# Flipdot.net
KiCad netlist of a schematic drawn in EAGLE
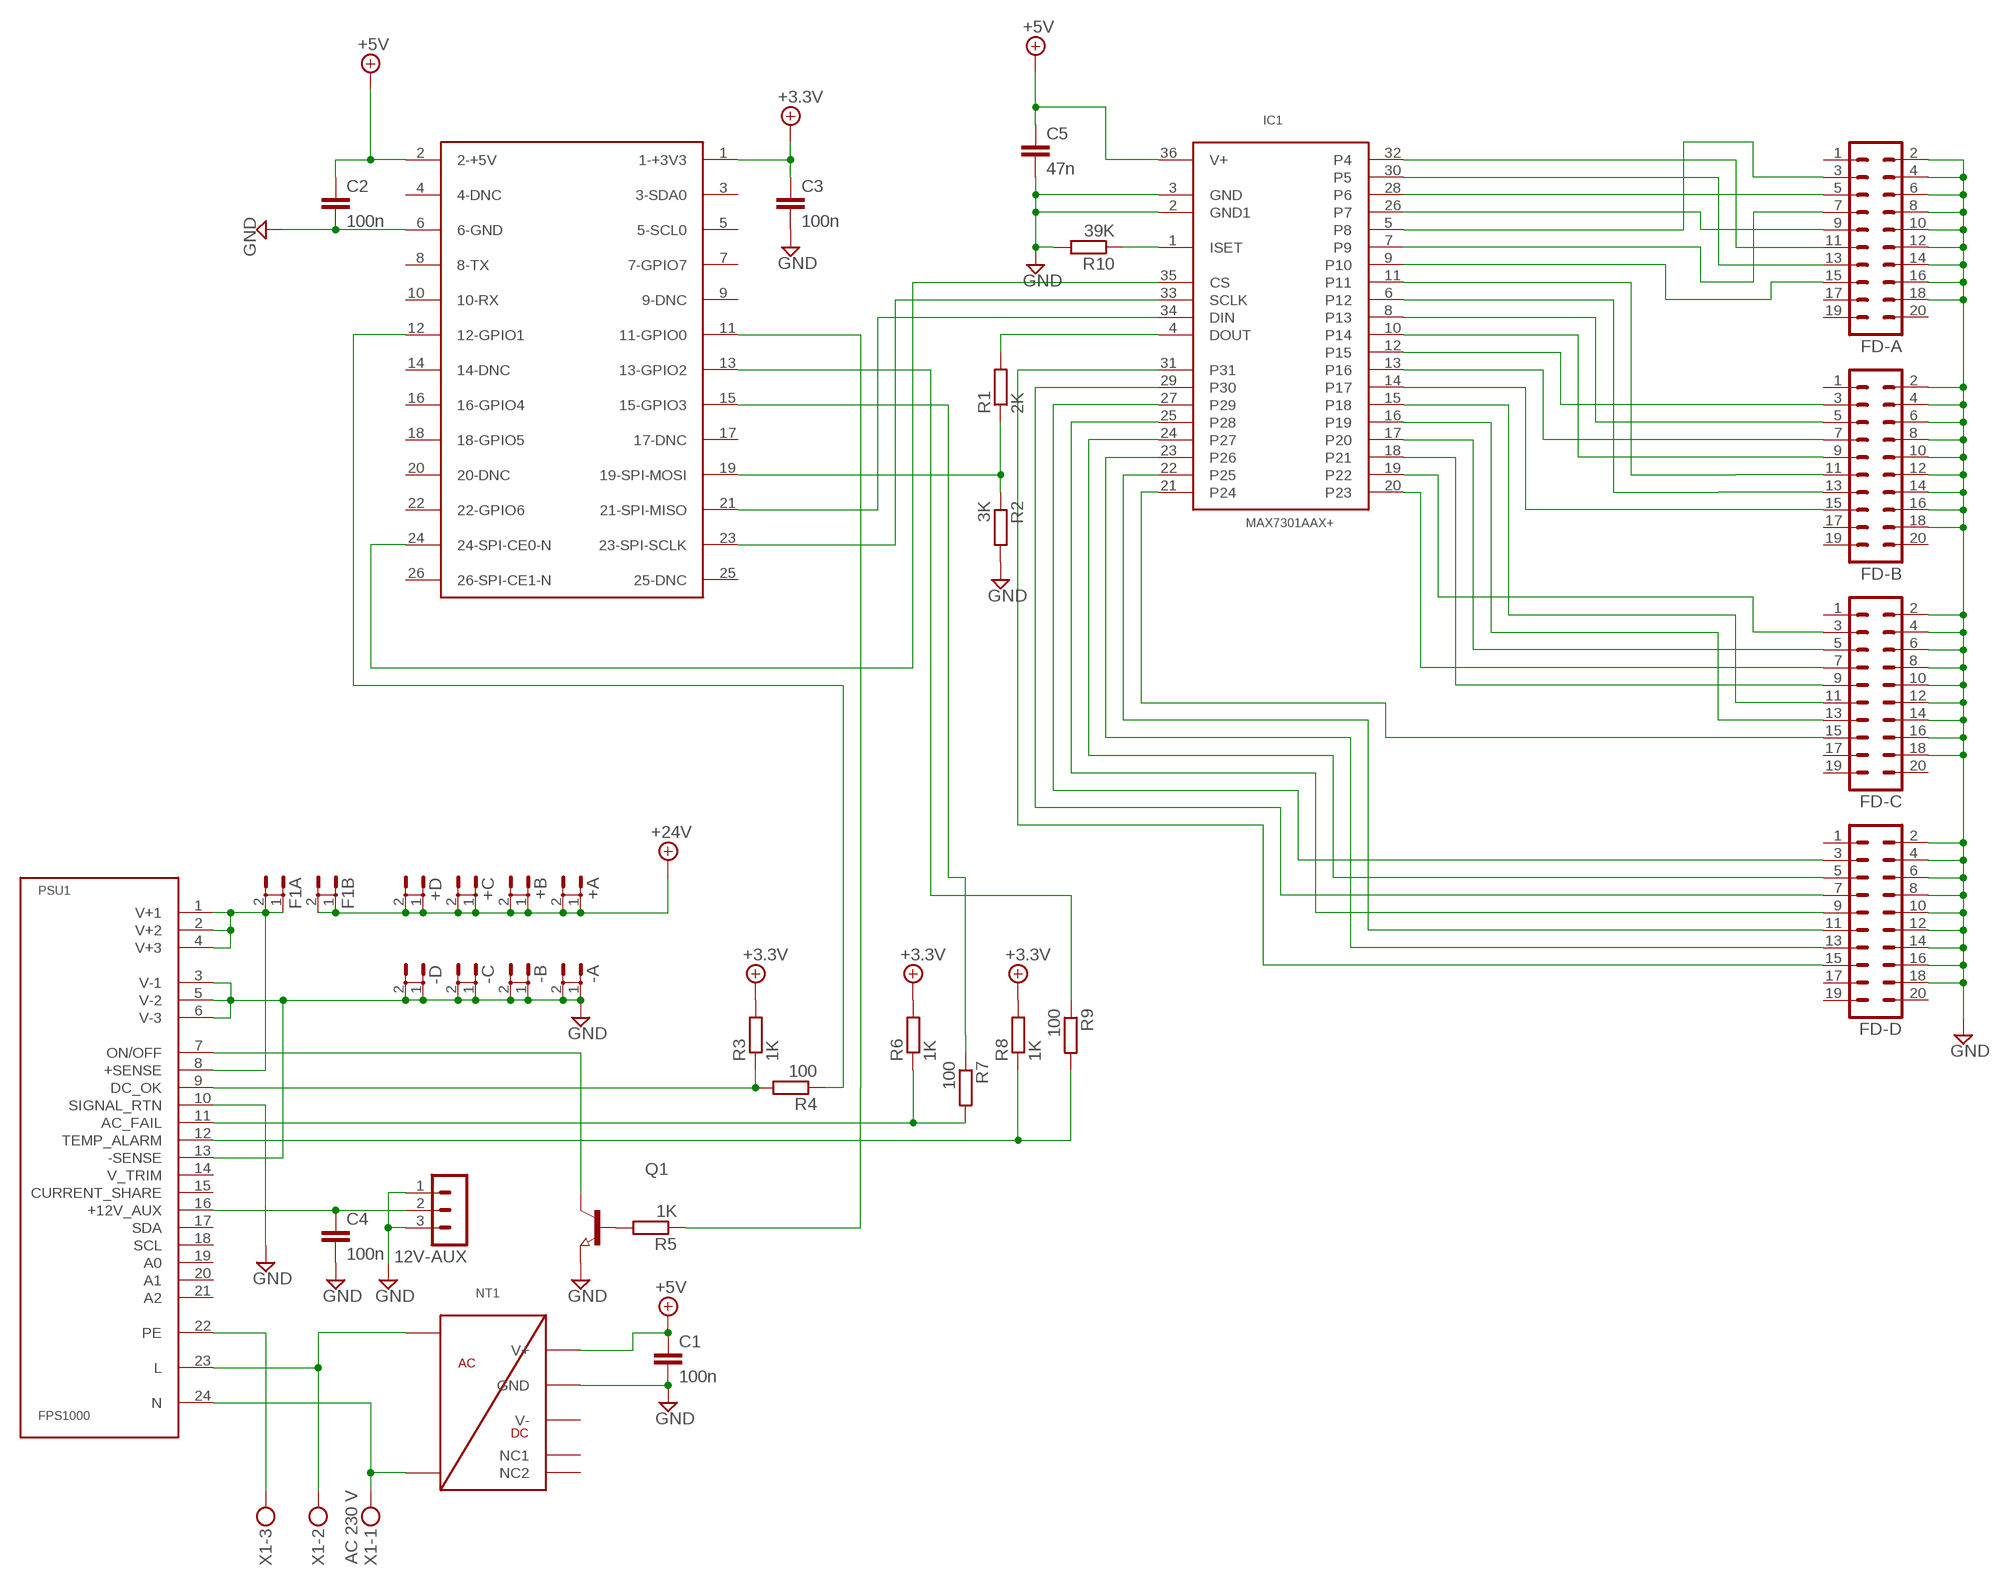
[diagram p0: schematic, sheet 1]

(export (version "E")
  (design (tool "Eeschema 10.0.6"))
  (components
    (comp (ref "+A")
      (value "ST6,3")
      (footprint "eagle-import:ST6,3")
      (libsource (lib "eagle-import") (part "ST6,3"))
    )
    (comp (ref "+B")
      (value "ST6,3")
      (footprint "eagle-import:ST6,3")
      (libsource (lib "eagle-import") (part "ST6,3"))
    )
    (comp (ref "+C")
      (value "ST6,3")
      (footprint "eagle-import:ST6,3")
      (libsource (lib "eagle-import") (part "ST6,3"))
    )
    (comp (ref "+D")
      (value "ST6,3")
      (footprint "eagle-import:ST6,3")
      (libsource (lib "eagle-import") (part "ST6,3"))
    )
    (comp (ref "-A")
      (value "ST6,3")
      (footprint "eagle-import:ST6,3")
      (libsource (lib "eagle-import") (part "ST6,3"))
    )
    (comp (ref "-B")
      (value "ST6,3")
      (footprint "eagle-import:ST6,3")
      (libsource (lib "eagle-import") (part "ST6,3"))
    )
    (comp (ref "-C")
      (value "ST6,3")
      (footprint "eagle-import:ST6,3")
      (libsource (lib "eagle-import") (part "ST6,3"))
    )
    (comp (ref "-D")
      (value "ST6,3")
      (footprint "eagle-import:ST6,3")
      (libsource (lib "eagle-import") (part "ST6,3"))
    )
    (comp (ref "12V-AUX")
      (value "MA03-1")
      (footprint "eagle-import:MA03-1")
      (libsource (lib "eagle-import") (part "MA03-1"))
    )
    (comp (ref "C1")
      (value "100n")
      (footprint "eagle-import:C0603")
      (libsource (lib "eagle-import") (part "C-EUC0603"))
    )
    (comp (ref "C2")
      (value "100n")
      (footprint "eagle-import:C0603")
      (libsource (lib "eagle-import") (part "C-EUC0603"))
    )
    (comp (ref "C3")
      (value "100n")
      (footprint "eagle-import:C0603")
      (libsource (lib "eagle-import") (part "C-EUC0603"))
    )
    (comp (ref "C4")
      (value "100n")
      (footprint "eagle-import:C0603")
      (libsource (lib "eagle-import") (part "C-EUC0603"))
    )
    (comp (ref "C5")
      (value "47n")
      (footprint "eagle-import:C0603")
      (libsource (lib "eagle-import") (part "C-EUC0603"))
    )
    (comp (ref "F1A")
      (value "ST6,3")
      (footprint "eagle-import:ST6,3")
      (libsource (lib "eagle-import") (part "ST6,3"))
    )
    (comp (ref "F1B")
      (value "ST6,3")
      (footprint "eagle-import:ST6,3")
      (libsource (lib "eagle-import") (part "ST6,3"))
    )
    (comp (ref "FD-A")
      (value "MA10-2")
      (footprint "eagle-import:MA10-2")
      (libsource (lib "eagle-import") (part "MA10-2"))
    )
    (comp (ref "FD-B")
      (value "MA10-2")
      (footprint "eagle-import:MA10-2")
      (fields (field (name "OC_FARNELL") "unknown") (field (name "OC_NEWARK") "unknown"))
      (libsource (lib "eagle-import") (part "MA10-2"))
    )
    (comp (ref "FD-C")
      (value "MA10-2")
      (footprint "eagle-import:MA10-2")
      (fields (field (name "OC_FARNELL") "unknown") (field (name "OC_NEWARK") "unknown"))
      (libsource (lib "eagle-import") (part "MA10-2"))
    )
    (comp (ref "FD-D")
      (value "MA10-2")
      (footprint "eagle-import:MA10-2")
      (fields (field (name "OC_FARNELL") "unknown") (field (name "OC_NEWARK") "unknown"))
      (libsource (lib "eagle-import") (part "MA10-2"))
    )
    (comp (ref "IC1")
      (value "MAX7301AAX+")
      (footprint "eagle-import:SSOP36")
      (libsource (lib "eagle-import") (part "MAX7301AAX+"))
    )
    (comp (ref "NT1")
      (value "TMPM04")
      (footprint "eagle-import:TPM04")
      (libsource (lib "eagle-import") (part "TMPM04"))
    )
    (comp (ref "PSU1")
      (value "FPS1000")
      (footprint "eagle-import:24W9F")
      (libsource (lib "eagle-import") (part "FPS1000"))
    )
    (comp (ref "Q1")
      (value "NPN-TRANSISTOR_SOT23")
      (footprint "eagle-import:SOT23")
      (libsource (lib "eagle-import") (part "NPN-TRANSISTOR_SOT23"))
    )
    (comp (ref "R1")
      (value "2K")
      (footprint "eagle-import:R0603")
      (libsource (lib "eagle-import") (part "R-EU_R0603"))
    )
    (comp (ref "R2")
      (value "3K")
      (footprint "eagle-import:R0603")
      (libsource (lib "eagle-import") (part "R-EU_R0603"))
    )
    (comp (ref "R3")
      (value "1K")
      (footprint "eagle-import:R0603")
      (libsource (lib "eagle-import") (part "R-EU_R0603"))
    )
    (comp (ref "R4")
      (value "100")
      (footprint "eagle-import:R0603")
      (libsource (lib "eagle-import") (part "R-EU_R0603"))
    )
    (comp (ref "R5")
      (value "1K")
      (footprint "eagle-import:R0603")
      (libsource (lib "eagle-import") (part "R-EU_R0603"))
    )
    (comp (ref "R6")
      (value "1K")
      (footprint "eagle-import:R0603")
      (libsource (lib "eagle-import") (part "R-EU_R0603"))
    )
    (comp (ref "R7")
      (value "100")
      (footprint "eagle-import:R0603")
      (libsource (lib "eagle-import") (part "R-EU_R0603"))
    )
    (comp (ref "R8")
      (value "1K")
      (footprint "eagle-import:R0603")
      (libsource (lib "eagle-import") (part "R-EU_R0603"))
    )
    (comp (ref "R9")
      (value "100")
      (footprint "eagle-import:R0603")
      (libsource (lib "eagle-import") (part "R-EU_R0603"))
    )
    (comp (ref "R10")
      (value "39K")
      (footprint "eagle-import:R0603")
      (libsource (lib "eagle-import") (part "R-EU_R0603"))
    )
    (comp (ref "U$1")
      (value "RASPBERRY-PI")
      (footprint "eagle-import:RASPBERRY-PI")
      (libsource (lib "eagle-import") (part "RASPBERRY-PI"))
    )
    (comp (ref "X1")
      (value "AC 230 V")
      (footprint "eagle-import:MKDSN1,5_3-5,08")
      (fields (field (name "MPN") "SMKDSN1,5/3-5,08"))
      (libsource (lib "eagle-import") (part "MKDSN1,5/3-5,08"))
    )
  )
  (nets
    (net (code "1") (name "+3.3V") (class "Default")
      (node (ref "C3") (pin "1") (pinfunction "1_1") (pintype "passive"))
      (node (ref "R3") (pin "2") (pinfunction "2_2") (pintype "passive"))
      (node (ref "R6") (pin "2") (pinfunction "2_2") (pintype "passive"))
      (node (ref "R8") (pin "2") (pinfunction "2_2") (pintype "passive"))
      (node (ref "U$1") (pin "1") (pinfunction "1-+3V3_1") (pintype "bidirectional"))
    )
    (net (code "2") (name "+5V") (class "Default")
      (node (ref "C1") (pin "1") (pinfunction "1_1") (pintype "passive"))
      (node (ref "C2") (pin "1") (pinfunction "1_1") (pintype "passive"))
      (node (ref "C5") (pin "1") (pinfunction "1_1") (pintype "passive"))
      (node (ref "IC1") (pin "36") (pinfunction "V+_36") (pintype "power_in"))
      (node (ref "NT1") (pin "3") (pinfunction "V+_3") (pintype "power_in"))
      (node (ref "U$1") (pin "2") (pinfunction "2-+5V_2") (pintype "bidirectional"))
    )
    (net (code "3") (name "+24V") (class "Default")
      (node (ref "+A") (pin "1") (pinfunction "1_1") (pintype "passive"))
      (node (ref "+A") (pin "2") (pinfunction "2_2") (pintype "passive"))
      (node (ref "+B") (pin "1") (pinfunction "1_1") (pintype "passive"))
      (node (ref "+B") (pin "2") (pinfunction "2_2") (pintype "passive"))
      (node (ref "+C") (pin "1") (pinfunction "1_1") (pintype "passive"))
      (node (ref "+C") (pin "2") (pinfunction "2_2") (pintype "passive"))
      (node (ref "+D") (pin "1") (pinfunction "1_1") (pintype "passive"))
      (node (ref "+D") (pin "2") (pinfunction "2_2") (pintype "passive"))
      (node (ref "F1B") (pin "1") (pinfunction "1_1") (pintype "passive"))
      (node (ref "F1B") (pin "2") (pinfunction "2_2") (pintype "passive"))
    )
    (net (code "4") (name "/NC1") (class "Default")
      (node (ref "NT1") (pin "1") (pinfunction "NC1_1") (pintype "power_in"))
    )
    (net (code "5") (name "/NC2") (class "Default")
      (node (ref "NT1") (pin "2") (pinfunction "NC2_2") (pintype "power_in"))
    )
    (net (code "6") (name "/V-") (class "Default")
      (node (ref "NT1") (pin "5") (pinfunction "V-_5") (pintype "power_in"))
    )
    (net (code "7") (name "GND") (class "Default")
      (node (ref "-A") (pin "1") (pinfunction "1_1") (pintype "passive"))
      (node (ref "-A") (pin "2") (pinfunction "2_2") (pintype "passive"))
      (node (ref "-B") (pin "1") (pinfunction "1_1") (pintype "passive"))
      (node (ref "-B") (pin "2") (pinfunction "2_2") (pintype "passive"))
      (node (ref "-C") (pin "1") (pinfunction "1_1") (pintype "passive"))
      (node (ref "-C") (pin "2") (pinfunction "2_2") (pintype "passive"))
      (node (ref "-D") (pin "1") (pinfunction "1_1") (pintype "passive"))
      (node (ref "-D") (pin "2") (pinfunction "2_2") (pintype "passive"))
      (node (ref "12V-AUX") (pin "1") (pinfunction "1_1") (pintype "passive"))
      (node (ref "12V-AUX") (pin "3") (pinfunction "3_3") (pintype "passive"))
      (node (ref "C1") (pin "2") (pinfunction "2_2") (pintype "passive"))
      (node (ref "C2") (pin "2") (pinfunction "2_2") (pintype "passive"))
      (node (ref "C3") (pin "2") (pinfunction "2_2") (pintype "passive"))
      (node (ref "C4") (pin "2") (pinfunction "2_2") (pintype "passive"))
      (node (ref "C5") (pin "2") (pinfunction "2_2") (pintype "passive"))
      (node (ref "FD-A") (pin "10") (pinfunction "10_10") (pintype "passive"))
      (node (ref "FD-A") (pin "12") (pinfunction "12_12") (pintype "passive"))
      (node (ref "FD-A") (pin "14") (pinfunction "14_14") (pintype "passive"))
      (node (ref "FD-A") (pin "16") (pinfunction "16_16") (pintype "passive"))
      (node (ref "FD-A") (pin "18") (pinfunction "18_18") (pintype "passive"))
      (node (ref "FD-A") (pin "2") (pinfunction "2_2") (pintype "passive"))
      (node (ref "FD-A") (pin "4") (pinfunction "4_4") (pintype "passive"))
      (node (ref "FD-A") (pin "6") (pinfunction "6_6") (pintype "passive"))
      (node (ref "FD-A") (pin "8") (pinfunction "8_8") (pintype "passive"))
      (node (ref "FD-B") (pin "10") (pinfunction "10_10") (pintype "passive"))
      (node (ref "FD-B") (pin "12") (pinfunction "12_12") (pintype "passive"))
      (node (ref "FD-B") (pin "14") (pinfunction "14_14") (pintype "passive"))
      (node (ref "FD-B") (pin "16") (pinfunction "16_16") (pintype "passive"))
      (node (ref "FD-B") (pin "18") (pinfunction "18_18") (pintype "passive"))
      (node (ref "FD-B") (pin "2") (pinfunction "2_2") (pintype "passive"))
      (node (ref "FD-B") (pin "4") (pinfunction "4_4") (pintype "passive"))
      (node (ref "FD-B") (pin "6") (pinfunction "6_6") (pintype "passive"))
      (node (ref "FD-B") (pin "8") (pinfunction "8_8") (pintype "passive"))
      (node (ref "FD-C") (pin "10") (pinfunction "10_10") (pintype "passive"))
      (node (ref "FD-C") (pin "12") (pinfunction "12_12") (pintype "passive"))
      (node (ref "FD-C") (pin "14") (pinfunction "14_14") (pintype "passive"))
      (node (ref "FD-C") (pin "16") (pinfunction "16_16") (pintype "passive"))
      (node (ref "FD-C") (pin "18") (pinfunction "18_18") (pintype "passive"))
      (node (ref "FD-C") (pin "2") (pinfunction "2_2") (pintype "passive"))
      (node (ref "FD-C") (pin "4") (pinfunction "4_4") (pintype "passive"))
      (node (ref "FD-C") (pin "6") (pinfunction "6_6") (pintype "passive"))
      (node (ref "FD-C") (pin "8") (pinfunction "8_8") (pintype "passive"))
      (node (ref "FD-D") (pin "10") (pinfunction "10_10") (pintype "passive"))
      (node (ref "FD-D") (pin "12") (pinfunction "12_12") (pintype "passive"))
      (node (ref "FD-D") (pin "14") (pinfunction "14_14") (pintype "passive"))
      (node (ref "FD-D") (pin "16") (pinfunction "16_16") (pintype "passive"))
      (node (ref "FD-D") (pin "18") (pinfunction "18_18") (pintype "passive"))
      (node (ref "FD-D") (pin "2") (pinfunction "2_2") (pintype "passive"))
      (node (ref "FD-D") (pin "4") (pinfunction "4_4") (pintype "passive"))
      (node (ref "FD-D") (pin "6") (pinfunction "6_6") (pintype "passive"))
      (node (ref "FD-D") (pin "8") (pinfunction "8_8") (pintype "passive"))
      (node (ref "IC1") (pin "2") (pinfunction "GND1_2") (pintype "power_in"))
      (node (ref "IC1") (pin "3") (pinfunction "GND_3") (pintype "power_in"))
      (node (ref "NT1") (pin "4") (pinfunction "GND_4") (pintype "power_in"))
      (node (ref "PSU1") (pin "10") (pinfunction "SIGNAL_RTN_10") (pintype "bidirectional"))
      (node (ref "PSU1") (pin "13") (pinfunction "-SENSE_13") (pintype "bidirectional"))
      (node (ref "PSU1") (pin "3") (pinfunction "V-1_3") (pintype "power_in"))
      (node (ref "PSU1") (pin "5") (pinfunction "V-2_5") (pintype "power_in"))
      (node (ref "PSU1") (pin "6") (pinfunction "V-3_6") (pintype "power_in"))
      (node (ref "Q1") (pin "2") (pinfunction "E_2") (pintype "passive"))
      (node (ref "R10") (pin "2") (pinfunction "2_2") (pintype "passive"))
      (node (ref "R2") (pin "2") (pinfunction "2_2") (pintype "passive"))
      (node (ref "U$1") (pin "6") (pinfunction "6-GND_6") (pintype "bidirectional"))
    )
    (net (code "8") (name "Net-(IC1-CS)") (class "Default")
      (node (ref "IC1") (pin "35") (pinfunction "CS_35") (pintype "bidirectional"))
      (node (ref "U$1") (pin "24") (pinfunction "24-SPI-CE0-N_24") (pintype "bidirectional"))
    )
    (net (code "9") (name "Net-(IC1-DIN)") (class "Default")
      (node (ref "IC1") (pin "34") (pinfunction "DIN_34") (pintype "bidirectional"))
      (node (ref "U$1") (pin "21") (pinfunction "21-SPI-MISO_21") (pintype "bidirectional"))
    )
    (net (code "10") (name "Net-(IC1-DOUT)") (class "Default")
      (node (ref "IC1") (pin "4") (pinfunction "DOUT_4") (pintype "bidirectional"))
      (node (ref "R1") (pin "2") (pinfunction "2_2") (pintype "passive"))
    )
    (net (code "11") (name "Net-(IC1-ISET)") (class "Default")
      (node (ref "IC1") (pin "1") (pinfunction "ISET_1") (pintype "bidirectional"))
      (node (ref "R10") (pin "1") (pinfunction "1_1") (pintype "passive"))
    )
    (net (code "12") (name "Net-(IC1-P4)") (class "Default")
      (node (ref "FD-A") (pin "11") (pinfunction "11_11") (pintype "passive"))
      (node (ref "IC1") (pin "32") (pinfunction "P4_32") (pintype "bidirectional"))
    )
    (net (code "13") (name "Net-(IC1-P5)") (class "Default")
      (node (ref "FD-A") (pin "13") (pinfunction "13_13") (pintype "passive"))
      (node (ref "IC1") (pin "30") (pinfunction "P5_30") (pintype "bidirectional"))
    )
    (net (code "14") (name "Net-(IC1-P6)") (class "Default")
      (node (ref "FD-A") (pin "5") (pinfunction "5_5") (pintype "passive"))
      (node (ref "IC1") (pin "28") (pinfunction "P6_28") (pintype "bidirectional"))
    )
    (net (code "15") (name "Net-(IC1-P7)") (class "Default")
      (node (ref "FD-A") (pin "9") (pinfunction "9_9") (pintype "passive"))
      (node (ref "IC1") (pin "26") (pinfunction "P7_26") (pintype "bidirectional"))
    )
    (net (code "16") (name "Net-(IC1-P8)") (class "Default")
      (node (ref "FD-A") (pin "3") (pinfunction "3_3") (pintype "passive"))
      (node (ref "IC1") (pin "5") (pinfunction "P8_5") (pintype "bidirectional"))
    )
    (net (code "17") (name "Net-(IC1-P9)") (class "Default")
      (node (ref "FD-A") (pin "7") (pinfunction "7_7") (pintype "passive"))
      (node (ref "IC1") (pin "7") (pinfunction "P9_7") (pintype "bidirectional"))
    )
    (net (code "18") (name "Net-(IC1-P10)") (class "Default")
      (node (ref "FD-A") (pin "15") (pinfunction "15_15") (pintype "passive"))
      (node (ref "IC1") (pin "9") (pinfunction "P10_9") (pintype "bidirectional"))
    )
    (net (code "19") (name "Net-(IC1-P11)") (class "Default")
      (node (ref "FD-B") (pin "11") (pinfunction "11_11") (pintype "passive"))
      (node (ref "IC1") (pin "11") (pinfunction "P11_11") (pintype "bidirectional"))
    )
    (net (code "20") (name "Net-(IC1-P12)") (class "Default")
      (node (ref "FD-B") (pin "13") (pinfunction "13_13") (pintype "passive"))
      (node (ref "IC1") (pin "6") (pinfunction "P12_6") (pintype "bidirectional"))
    )
    (net (code "21") (name "Net-(IC1-P13)") (class "Default")
      (node (ref "FD-B") (pin "5") (pinfunction "5_5") (pintype "passive"))
      (node (ref "IC1") (pin "8") (pinfunction "P13_8") (pintype "bidirectional"))
    )
    (net (code "22") (name "Net-(IC1-P14)") (class "Default")
      (node (ref "FD-B") (pin "9") (pinfunction "9_9") (pintype "passive"))
      (node (ref "IC1") (pin "10") (pinfunction "P14_10") (pintype "bidirectional"))
    )
    (net (code "23") (name "Net-(IC1-P15)") (class "Default")
      (node (ref "FD-B") (pin "3") (pinfunction "3_3") (pintype "passive"))
      (node (ref "IC1") (pin "12") (pinfunction "P15_12") (pintype "bidirectional"))
    )
    (net (code "24") (name "Net-(IC1-P16)") (class "Default")
      (node (ref "FD-B") (pin "7") (pinfunction "7_7") (pintype "passive"))
      (node (ref "IC1") (pin "13") (pinfunction "P16_13") (pintype "bidirectional"))
    )
    (net (code "25") (name "Net-(IC1-P17)") (class "Default")
      (node (ref "FD-B") (pin "15") (pinfunction "15_15") (pintype "passive"))
      (node (ref "IC1") (pin "14") (pinfunction "P17_14") (pintype "bidirectional"))
    )
    (net (code "26") (name "Net-(IC1-P18)") (class "Default")
      (node (ref "FD-C") (pin "11") (pinfunction "11_11") (pintype "passive"))
      (node (ref "IC1") (pin "15") (pinfunction "P18_15") (pintype "bidirectional"))
    )
    (net (code "27") (name "Net-(IC1-P19)") (class "Default")
      (node (ref "FD-C") (pin "13") (pinfunction "13_13") (pintype "passive"))
      (node (ref "IC1") (pin "16") (pinfunction "P19_16") (pintype "bidirectional"))
    )
    (net (code "28") (name "Net-(IC1-P20)") (class "Default")
      (node (ref "FD-C") (pin "5") (pinfunction "5_5") (pintype "passive"))
      (node (ref "IC1") (pin "17") (pinfunction "P20_17") (pintype "bidirectional"))
    )
    (net (code "29") (name "Net-(IC1-P21)") (class "Default")
      (node (ref "FD-C") (pin "9") (pinfunction "9_9") (pintype "passive"))
      (node (ref "IC1") (pin "18") (pinfunction "P21_18") (pintype "bidirectional"))
    )
    (net (code "30") (name "Net-(IC1-P22)") (class "Default")
      (node (ref "FD-C") (pin "3") (pinfunction "3_3") (pintype "passive"))
      (node (ref "IC1") (pin "19") (pinfunction "P22_19") (pintype "bidirectional"))
    )
    (net (code "31") (name "Net-(IC1-P23)") (class "Default")
      (node (ref "FD-C") (pin "7") (pinfunction "7_7") (pintype "passive"))
      (node (ref "IC1") (pin "20") (pinfunction "P23_20") (pintype "bidirectional"))
    )
    (net (code "32") (name "Net-(IC1-P24)") (class "Default")
      (node (ref "FD-C") (pin "15") (pinfunction "15_15") (pintype "passive"))
      (node (ref "IC1") (pin "21") (pinfunction "P24_21") (pintype "bidirectional"))
    )
    (net (code "33") (name "Net-(IC1-P25)") (class "Default")
      (node (ref "FD-D") (pin "11") (pinfunction "11_11") (pintype "passive"))
      (node (ref "IC1") (pin "22") (pinfunction "P25_22") (pintype "bidirectional"))
    )
    (net (code "34") (name "Net-(IC1-P26)") (class "Default")
      (node (ref "FD-D") (pin "13") (pinfunction "13_13") (pintype "passive"))
      (node (ref "IC1") (pin "23") (pinfunction "P26_23") (pintype "bidirectional"))
    )
    (net (code "35") (name "Net-(IC1-P27)") (class "Default")
      (node (ref "FD-D") (pin "5") (pinfunction "5_5") (pintype "passive"))
      (node (ref "IC1") (pin "24") (pinfunction "P27_24") (pintype "bidirectional"))
    )
    (net (code "36") (name "Net-(IC1-P28)") (class "Default")
      (node (ref "FD-D") (pin "9") (pinfunction "9_9") (pintype "passive"))
      (node (ref "IC1") (pin "25") (pinfunction "P28_25") (pintype "bidirectional"))
    )
    (net (code "37") (name "Net-(IC1-P29)") (class "Default")
      (node (ref "FD-D") (pin "3") (pinfunction "3_3") (pintype "passive"))
      (node (ref "IC1") (pin "27") (pinfunction "P29_27") (pintype "bidirectional"))
    )
    (net (code "38") (name "Net-(IC1-P30)") (class "Default")
      (node (ref "FD-D") (pin "7") (pinfunction "7_7") (pintype "passive"))
      (node (ref "IC1") (pin "29") (pinfunction "P30_29") (pintype "bidirectional"))
    )
    (net (code "39") (name "Net-(IC1-P31)") (class "Default")
      (node (ref "FD-D") (pin "15") (pinfunction "15_15") (pintype "passive"))
      (node (ref "IC1") (pin "31") (pinfunction "P31_31") (pintype "bidirectional"))
    )
    (net (code "40") (name "Net-(IC1-SCLK)") (class "Default")
      (node (ref "IC1") (pin "33") (pinfunction "SCLK_33") (pintype "bidirectional"))
      (node (ref "U$1") (pin "23") (pinfunction "23-SPI-SCLK_23") (pintype "bidirectional"))
    )
    (net (code "41") (name "Net-(NT1-L)") (class "Default")
      (node (ref "NT1") (pin "7") (pinfunction "L_7") (pintype "power_in"))
      (node (ref "PSU1") (pin "23") (pinfunction "L_23") (pintype "bidirectional"))
      (node (ref "X1") (pin "2") (pinfunction "KL_2") (pintype "passive"))
    )
    (net (code "42") (name "Net-(NT1-N)") (class "Default")
      (node (ref "NT1") (pin "6") (pinfunction "N_6") (pintype "power_in"))
      (node (ref "PSU1") (pin "24") (pinfunction "N_24") (pintype "bidirectional"))
      (node (ref "X1") (pin "1") (pinfunction "KL_1") (pintype "passive"))
    )
    (net (code "43") (name "Net-(PSU1-+12V_AUX)") (class "Default")
      (node (ref "12V-AUX") (pin "2") (pinfunction "2_2") (pintype "passive"))
      (node (ref "C4") (pin "1") (pinfunction "1_1") (pintype "passive"))
      (node (ref "PSU1") (pin "16") (pinfunction "+12V_AUX_16") (pintype "bidirectional"))
    )
    (net (code "44") (name "Net-(PSU1-+SENSE)") (class "Default")
      (node (ref "F1A") (pin "1") (pinfunction "1_1") (pintype "passive"))
      (node (ref "F1A") (pin "2") (pinfunction "2_2") (pintype "passive"))
      (node (ref "PSU1") (pin "1") (pinfunction "V+1_1") (pintype "power_in"))
      (node (ref "PSU1") (pin "2") (pinfunction "V+2_2") (pintype "power_in"))
      (node (ref "PSU1") (pin "4") (pinfunction "V+3_4") (pintype "power_in"))
      (node (ref "PSU1") (pin "8") (pinfunction "+SENSE_8") (pintype "bidirectional"))
    )
    (net (code "45") (name "Net-(PSU1-AC_FAIL)") (class "Default")
      (node (ref "PSU1") (pin "11") (pinfunction "AC_FAIL_11") (pintype "bidirectional"))
      (node (ref "R6") (pin "1") (pinfunction "1_1") (pintype "passive"))
      (node (ref "R7") (pin "2") (pinfunction "2_2") (pintype "passive"))
    )
    (net (code "46") (name "Net-(PSU1-DC_OK)") (class "Default")
      (node (ref "PSU1") (pin "9") (pinfunction "DC_OK_9") (pintype "bidirectional"))
      (node (ref "R3") (pin "1") (pinfunction "1_1") (pintype "passive"))
      (node (ref "R4") (pin "2") (pinfunction "2_2") (pintype "passive"))
    )
    (net (code "47") (name "Net-(PSU1-ON{slash}OFF)") (class "Default")
      (node (ref "PSU1") (pin "7") (pinfunction "ON/OFF_7") (pintype "bidirectional"))
      (node (ref "Q1") (pin "3") (pinfunction "C_3") (pintype "passive"))
    )
    (net (code "48") (name "Net-(PSU1-PE)") (class "Default")
      (node (ref "PSU1") (pin "22") (pinfunction "PE_22") (pintype "bidirectional"))
      (node (ref "X1") (pin "3") (pinfunction "KL_3") (pintype "passive"))
    )
    (net (code "49") (name "Net-(PSU1-TEMP_ALARM)") (class "Default")
      (node (ref "PSU1") (pin "12") (pinfunction "TEMP_ALARM_12") (pintype "bidirectional"))
      (node (ref "R8") (pin "1") (pinfunction "1_1") (pintype "passive"))
      (node (ref "R9") (pin "2") (pinfunction "2_2") (pintype "passive"))
    )
    (net (code "50") (name "Net-(Q1-B)") (class "Default")
      (node (ref "Q1") (pin "1") (pinfunction "B_1") (pintype "passive"))
      (node (ref "R5") (pin "2") (pinfunction "2_2") (pintype "passive"))
    )
    (net (code "51") (name "Net-(U$1-11-GPIO0)") (class "Default")
      (node (ref "R5") (pin "1") (pinfunction "1_1") (pintype "passive"))
      (node (ref "U$1") (pin "11") (pinfunction "11-GPIO0_11") (pintype "bidirectional"))
    )
    (net (code "52") (name "Net-(U$1-12-GPIO1)") (class "Default")
      (node (ref "R4") (pin "1") (pinfunction "1_1") (pintype "passive"))
      (node (ref "U$1") (pin "12") (pinfunction "12-GPIO1_12") (pintype "bidirectional"))
    )
    (net (code "53") (name "Net-(U$1-13-GPIO2)") (class "Default")
      (node (ref "R9") (pin "1") (pinfunction "1_1") (pintype "passive"))
      (node (ref "U$1") (pin "13") (pinfunction "13-GPIO2_13") (pintype "bidirectional"))
    )
    (net (code "54") (name "Net-(U$1-15-GPIO3)") (class "Default")
      (node (ref "R7") (pin "1") (pinfunction "1_1") (pintype "passive"))
      (node (ref "U$1") (pin "15") (pinfunction "15-GPIO3_15") (pintype "bidirectional"))
    )
    (net (code "55") (name "Net-(U$1-19-SPI-MOSI)") (class "Default")
      (node (ref "R1") (pin "1") (pinfunction "1_1") (pintype "passive"))
      (node (ref "R2") (pin "1") (pinfunction "1_1") (pintype "passive"))
      (node (ref "U$1") (pin "19") (pinfunction "19-SPI-MOSI_19") (pintype "bidirectional"))
    )
    (net (code "56") (name "unconnected-(FD-A-Pad1)") (class "Default")
      (node (ref "FD-A") (pin "1") (pinfunction "1_1") (pintype "passive"))
    )
    (net (code "57") (name "unconnected-(FD-A-Pad17)") (class "Default")
      (node (ref "FD-A") (pin "17") (pinfunction "17_17") (pintype "passive"))
    )
    (net (code "58") (name "unconnected-(FD-A-Pad19)") (class "Default")
      (node (ref "FD-A") (pin "19") (pinfunction "19_19") (pintype "passive"))
    )
    (net (code "59") (name "unconnected-(FD-A-Pad20)") (class "Default")
      (node (ref "FD-A") (pin "20") (pinfunction "20_20") (pintype "passive"))
    )
    (net (code "60") (name "unconnected-(FD-B-Pad1)") (class "Default")
      (node (ref "FD-B") (pin "1") (pinfunction "1_1") (pintype "passive"))
    )
    (net (code "61") (name "unconnected-(FD-B-Pad17)") (class "Default")
      (node (ref "FD-B") (pin "17") (pinfunction "17_17") (pintype "passive"))
    )
    (net (code "62") (name "unconnected-(FD-B-Pad19)") (class "Default")
      (node (ref "FD-B") (pin "19") (pinfunction "19_19") (pintype "passive"))
    )
    (net (code "63") (name "unconnected-(FD-B-Pad20)") (class "Default")
      (node (ref "FD-B") (pin "20") (pinfunction "20_20") (pintype "passive"))
    )
    (net (code "64") (name "unconnected-(FD-C-Pad1)") (class "Default")
      (node (ref "FD-C") (pin "1") (pinfunction "1_1") (pintype "passive"))
    )
    (net (code "65") (name "unconnected-(FD-C-Pad17)") (class "Default")
      (node (ref "FD-C") (pin "17") (pinfunction "17_17") (pintype "passive"))
    )
    (net (code "66") (name "unconnected-(FD-C-Pad19)") (class "Default")
      (node (ref "FD-C") (pin "19") (pinfunction "19_19") (pintype "passive"))
    )
    (net (code "67") (name "unconnected-(FD-C-Pad20)") (class "Default")
      (node (ref "FD-C") (pin "20") (pinfunction "20_20") (pintype "passive"))
    )
    (net (code "68") (name "unconnected-(FD-D-Pad1)") (class "Default")
      (node (ref "FD-D") (pin "1") (pinfunction "1_1") (pintype "passive"))
    )
    (net (code "69") (name "unconnected-(FD-D-Pad17)") (class "Default")
      (node (ref "FD-D") (pin "17") (pinfunction "17_17") (pintype "passive"))
    )
    (net (code "70") (name "unconnected-(FD-D-Pad19)") (class "Default")
      (node (ref "FD-D") (pin "19") (pinfunction "19_19") (pintype "passive"))
    )
    (net (code "71") (name "unconnected-(FD-D-Pad20)") (class "Default")
      (node (ref "FD-D") (pin "20") (pinfunction "20_20") (pintype "passive"))
    )
    (net (code "72") (name "unconnected-(PSU1-A0-Pad19)") (class "Default")
      (node (ref "PSU1") (pin "19") (pinfunction "A0_19") (pintype "bidirectional"))
    )
    (net (code "73") (name "unconnected-(PSU1-A1-Pad20)") (class "Default")
      (node (ref "PSU1") (pin "20") (pinfunction "A1_20") (pintype "bidirectional"))
    )
    (net (code "74") (name "unconnected-(PSU1-A2-Pad21)") (class "Default")
      (node (ref "PSU1") (pin "21") (pinfunction "A2_21") (pintype "bidirectional"))
    )
    (net (code "75") (name "unconnected-(PSU1-CURRENT_SHARE-Pad15)") (class "Default")
      (node (ref "PSU1") (pin "15") (pinfunction "CURRENT_SHARE_15") (pintype "bidirectional"))
    )
    (net (code "76") (name "unconnected-(PSU1-SCL-Pad18)") (class "Default")
      (node (ref "PSU1") (pin "18") (pinfunction "SCL_18") (pintype "bidirectional"))
    )
    (net (code "77") (name "unconnected-(PSU1-SDA-Pad17)") (class "Default")
      (node (ref "PSU1") (pin "17") (pinfunction "SDA_17") (pintype "bidirectional"))
    )
    (net (code "78") (name "unconnected-(PSU1-V_TRIM-Pad14)") (class "Default")
      (node (ref "PSU1") (pin "14") (pinfunction "V_TRIM_14") (pintype "bidirectional"))
    )
    (net (code "79") (name "unconnected-(U$1-3-SDA0-Pad3)") (class "Default")
      (node (ref "U$1") (pin "3") (pinfunction "3-SDA0_3") (pintype "bidirectional"))
    )
    (net (code "80") (name "unconnected-(U$1-4-DNC-Pad4)") (class "Default")
      (node (ref "U$1") (pin "4") (pinfunction "4-DNC_4") (pintype "bidirectional"))
    )
    (net (code "81") (name "unconnected-(U$1-5-SCL0-Pad5)") (class "Default")
      (node (ref "U$1") (pin "5") (pinfunction "5-SCL0_5") (pintype "bidirectional"))
    )
    (net (code "82") (name "unconnected-(U$1-7-GPIO7-Pad7)") (class "Default")
      (node (ref "U$1") (pin "7") (pinfunction "7-GPIO7_7") (pintype "bidirectional"))
    )
    (net (code "83") (name "unconnected-(U$1-8-TX-Pad8)") (class "Default")
      (node (ref "U$1") (pin "8") (pinfunction "8-TX_8") (pintype "bidirectional"))
    )
    (net (code "84") (name "unconnected-(U$1-9-DNC-Pad9)") (class "Default")
      (node (ref "U$1") (pin "9") (pinfunction "9-DNC_9") (pintype "bidirectional"))
    )
    (net (code "85") (name "unconnected-(U$1-10-RX-Pad10)") (class "Default")
      (node (ref "U$1") (pin "10") (pinfunction "10-RX_10") (pintype "bidirectional"))
    )
    (net (code "86") (name "unconnected-(U$1-14-DNC-Pad14)") (class "Default")
      (node (ref "U$1") (pin "14") (pinfunction "14-DNC_14") (pintype "bidirectional"))
    )
    (net (code "87") (name "unconnected-(U$1-16-GPIO4-Pad16)") (class "Default")
      (node (ref "U$1") (pin "16") (pinfunction "16-GPIO4_16") (pintype "bidirectional"))
    )
    (net (code "88") (name "unconnected-(U$1-17-DNC-Pad17)") (class "Default")
      (node (ref "U$1") (pin "17") (pinfunction "17-DNC_17") (pintype "bidirectional"))
    )
    (net (code "89") (name "unconnected-(U$1-18-GPIO5-Pad18)") (class "Default")
      (node (ref "U$1") (pin "18") (pinfunction "18-GPIO5_18") (pintype "bidirectional"))
    )
    (net (code "90") (name "unconnected-(U$1-20-DNC-Pad20)") (class "Default")
      (node (ref "U$1") (pin "20") (pinfunction "20-DNC_20") (pintype "bidirectional"))
    )
    (net (code "91") (name "unconnected-(U$1-22-GPIO6-Pad22)") (class "Default")
      (node (ref "U$1") (pin "22") (pinfunction "22-GPIO6_22") (pintype "bidirectional"))
    )
    (net (code "92") (name "unconnected-(U$1-25-DNC-Pad25)") (class "Default")
      (node (ref "U$1") (pin "25") (pinfunction "25-DNC_25") (pintype "bidirectional"))
    )
    (net (code "93") (name "unconnected-(U$1-26-SPI-CE1-N-Pad26)") (class "Default")
      (node (ref "U$1") (pin "26") (pinfunction "26-SPI-CE1-N_26") (pintype "bidirectional"))
    )
  )
)
